# Sheet1.net
KiCad netlist of a schematic drawn in Altium Designer
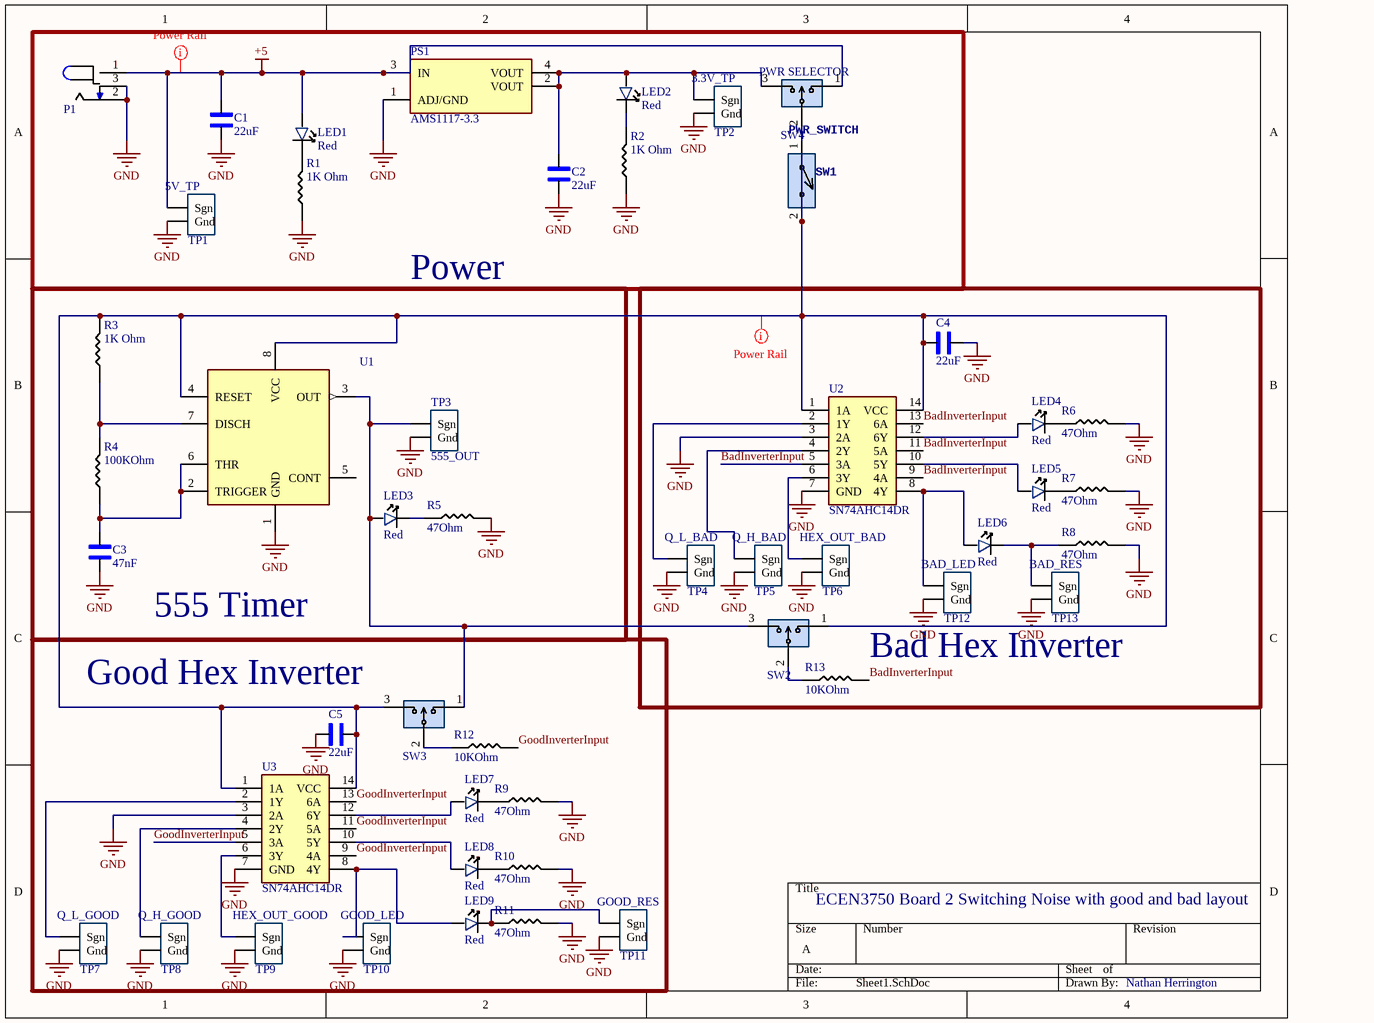
[diagram p0: Sheet1.SchDoc]

(export (version "E")
  (design (tool "Eeschema 10.0.6"))
  (components
    (comp (ref "C1")
      (value "22uF")
      (footprint "1206_Passive_Capacitor")
      (description "22uF ±10% 25V X5R 1206 Multilayer Ceramic Capacitors MLCC - SMD/SMT RoHS")
      (fields (field (name "MFR PART #") "CL31A226KAHNNNE") (field (name "LCSC PART#") "C12891"))
      (libsource (lib "ECEN5730Lib_2023_05_DS") (part "C_22uF_1206"))
    )
    (comp (ref "C2")
      (value "22uF")
      (footprint "1206_Passive_Capacitor")
      (description "22uF ±10% 25V X5R 1206 Multilayer Ceramic Capacitors MLCC - SMD/SMT RoHS")
      (fields (field (name "MFR PART #") "CL31A226KAHNNNE") (field (name "LCSC PART#") "C12891"))
      (libsource (lib "ECEN5730Lib_2023_05_DS") (part "C_22uF_1206"))
    )
    (comp (ref "C3")
      (value "47nF")
      (footprint "1206_Passive_Capacitor")
      (description "47nF ±5% 50V C0G 1206 Multilayer Ceramic Capacitors MLCC - SMD/SMT RoHS")
      (fields (field (name "LCSC PART#") "C21812") (field (name "MFR PART #") "GRM31M5C1H473JA01L"))
      (libsource (lib "ECEN5730Lib_2023_05_DS") (part "C_47nF_1206"))
    )
    (comp (ref "C4")
      (value "22uF")
      (footprint "1206_Passive_Capacitor")
      (description "22uF ±10% 25V X5R 1206 Multilayer Ceramic Capacitors MLCC - SMD/SMT RoHS")
      (fields (field (name "MFR PART #") "CL31A226KAHNNNE") (field (name "LCSC PART#") "C12891"))
      (libsource (lib "ECEN5730Lib_2023_05_DS") (part "C_22uF_1206"))
    )
    (comp (ref "C5")
      (value "22uF")
      (footprint "1206_Passive_Capacitor")
      (description "22uF ±10% 25V X5R 1206 Multilayer Ceramic Capacitors MLCC - SMD/SMT RoHS")
      (fields (field (name "MFR PART #") "CL31A226KAHNNNE") (field (name "LCSC PART#") "C12891"))
      (libsource (lib "ECEN5730Lib_2023_05_DS") (part "C_22uF_1206"))
    )
    (comp (ref "LED1")
      (value "Red")
      (footprint "LED_1206")
      (description "Red 621~631nm 1206 Light Emitting Diodes (LED) RoHS")
      (fields (field (name "MFR PART #") "15-21/R6C-FQ1R1B/2T") (field (name "LCSC PART#") "C93133"))
      (libsource (lib "ECEN5730Lib_2023_05_DS") (part "LED_RED_1206"))
    )
    (comp (ref "LED2")
      (value "Red")
      (footprint "LED_1206")
      (description "Red 621~631nm 1206 Light Emitting Diodes (LED) RoHS")
      (fields (field (name "MFR PART #") "15-21/R6C-FQ1R1B/2T") (field (name "LCSC PART#") "C93133"))
      (libsource (lib "ECEN5730Lib_2023_05_DS") (part "LED_RED_1206"))
    )
    (comp (ref "LED3")
      (value "Red")
      (footprint "LED_1206")
      (description "Red 621~631nm 1206 Light Emitting Diodes (LED) RoHS")
      (fields (field (name "MFR PART #") "15-21/R6C-FQ1R1B/2T") (field (name "LCSC PART#") "C93133"))
      (libsource (lib "ECEN5730Lib_2023_05_DS") (part "LED_RED_1206"))
    )
    (comp (ref "LED4")
      (value "Red")
      (footprint "LED_1206")
      (description "Red 621~631nm 1206 Light Emitting Diodes (LED) RoHS")
      (fields (field (name "MFR PART #") "15-21/R6C-FQ1R1B/2T") (field (name "LCSC PART#") "C93133"))
      (libsource (lib "ECEN5730Lib_2023_05_DS") (part "LED_RED_1206"))
    )
    (comp (ref "LED5")
      (value "Red")
      (footprint "LED_1206")
      (description "Red 621~631nm 1206 Light Emitting Diodes (LED) RoHS")
      (fields (field (name "MFR PART #") "15-21/R6C-FQ1R1B/2T") (field (name "LCSC PART#") "C93133"))
      (libsource (lib "ECEN5730Lib_2023_05_DS") (part "LED_RED_1206"))
    )
    (comp (ref "LED6")
      (value "Red")
      (footprint "LED_1206")
      (description "Red 621~631nm 1206 Light Emitting Diodes (LED) RoHS")
      (fields (field (name "MFR PART #") "15-21/R6C-FQ1R1B/2T") (field (name "LCSC PART#") "C93133"))
      (libsource (lib "ECEN5730Lib_2023_05_DS") (part "LED_RED_1206"))
    )
    (comp (ref "LED7")
      (value "Red")
      (footprint "LED_1206")
      (description "Red 621~631nm 1206 Light Emitting Diodes (LED) RoHS")
      (fields (field (name "MFR PART #") "15-21/R6C-FQ1R1B/2T") (field (name "LCSC PART#") "C93133"))
      (libsource (lib "ECEN5730Lib_2023_05_DS") (part "LED_RED_1206"))
    )
    (comp (ref "LED8")
      (value "Red")
      (footprint "LED_1206")
      (description "Red 621~631nm 1206 Light Emitting Diodes (LED) RoHS")
      (fields (field (name "MFR PART #") "15-21/R6C-FQ1R1B/2T") (field (name "LCSC PART#") "C93133"))
      (libsource (lib "ECEN5730Lib_2023_05_DS") (part "LED_RED_1206"))
    )
    (comp (ref "LED9")
      (value "Red")
      (footprint "LED_1206")
      (description "Red 621~631nm 1206 Light Emitting Diodes (LED) RoHS")
      (fields (field (name "MFR PART #") "15-21/R6C-FQ1R1B/2T") (field (name "LCSC PART#") "C93133"))
      (libsource (lib "ECEN5730Lib_2023_05_DS") (part "LED_RED_1206"))
    )
    (comp (ref "P1")
      (value "Power Jack")
      (footprint "Power_Jack")
      (description "Power Barrel Connector Jack 2.10mm ID (0.083\"), 5.50mm OD (0.217\") Through Hole, Right Angle")
      (fields (field (name "MFR PART #") "PJ-102A") (field (name "LCSC PART#") "C136744"))
      (libsource (lib "ECEN5730Lib_2023_05_DS") (part "P_Power Jack"))
    )
    (comp (ref "PS1")
      (value "AMS1117-3.3")
      (footprint "LDO")
      (description "LOW DROPOUT REGULATORS(LDO) POSITIVE FIXED 1.3V @ 800MA 15V 3.3V 1A SOT-223 ROHS")
      (fields (field (name "LCSC PART#") "C6186"))
      (libsource (lib "ECEN5730Lib_2023_05_DS") (part "PS_AMS_LDO_3v3"))
    )
    (comp (ref "R1")
      (value "1K Ohm")
      (footprint "1206_Passive_Resitor")
      (description "CHIP RESISTOR - SURFACE MOUNT 1KOHMS ±1% 1/4W 1206 ROHS")
      (fields (field (name "MFR PART #") "RNCP1206FTD1K00CT") (field (name "LCSC PART#") "C4410"))
      (libsource (lib "ECEN5730Lib_2023_05_DS") (part "R_1K_1206"))
    )
    (comp (ref "R2")
      (value "1K Ohm")
      (footprint "1206_Passive_Resitor")
      (description "CHIP RESISTOR - SURFACE MOUNT 1KOHMS ±1% 1/4W 1206 ROHS")
      (fields (field (name "MFR PART #") "RNCP1206FTD1K00CT") (field (name "LCSC PART#") "C4410"))
      (libsource (lib "ECEN5730Lib_2023_05_DS") (part "R_1K_1206"))
    )
    (comp (ref "R3")
      (value "1K Ohm")
      (footprint "1206_Passive_Resitor")
      (description "CHIP RESISTOR - SURFACE MOUNT 1KOHMS ±1% 1/4W 1206 ROHS")
      (fields (field (name "MFR PART #") "RNCP1206FTD1K00CT") (field (name "LCSC PART#") "C4410"))
      (libsource (lib "ECEN5730Lib_2023_05_DS") (part "R_1K_1206"))
    )
    (comp (ref "R4")
      (value "100KOhm")
      (footprint "1206_Passive_Resitor")
      (description "100kΩ ±1% 0.25W ±100ppm/℃ 1206 Chip Resistor - Surface Mount RoHS")
      (fields (field (name "LCSC PART#") "C17900") (field (name "MFR PART #") "1206W4F1003T5E"))
      (libsource (lib "ECEN5730Lib_2023_05_DS") (part "R_100KOhm_1206"))
    )
    (comp (ref "R5")
      (value "47Ohm")
      (footprint "1206_Passive_Resitor")
      (description "47Ω ±5% 0.25W ±200ppm/℃ 1206 Chip Resistor - Surface Mount RoHS")
      (fields (field (name "MFR PART #") "1206W4J0470T5E") (field (name "LCSC PART#") "C25384"))
      (libsource (lib "ECEN5730Lib_2023_05_DS") (part "R_47Ohm_1206"))
    )
    (comp (ref "R6")
      (value "47Ohm")
      (footprint "1206_Passive_Resitor")
      (description "47Ω ±5% 0.25W ±200ppm/℃ 1206 Chip Resistor - Surface Mount RoHS")
      (fields (field (name "MFR PART #") "1206W4J0470T5E") (field (name "LCSC PART#") "C25384"))
      (libsource (lib "ECEN5730Lib_2023_05_DS") (part "R_47Ohm_1206"))
    )
    (comp (ref "R7")
      (value "47Ohm")
      (footprint "1206_Passive_Resitor")
      (description "47Ω ±5% 0.25W ±200ppm/℃ 1206 Chip Resistor - Surface Mount RoHS")
      (fields (field (name "MFR PART #") "1206W4J0470T5E") (field (name "LCSC PART#") "C25384"))
      (libsource (lib "ECEN5730Lib_2023_05_DS") (part "R_47Ohm_1206"))
    )
    (comp (ref "R8")
      (value "47Ohm")
      (footprint "1206_Passive_Resitor")
      (description "47Ω ±5% 0.25W ±200ppm/℃ 1206 Chip Resistor - Surface Mount RoHS")
      (fields (field (name "MFR PART #") "1206W4J0470T5E") (field (name "LCSC PART#") "C25384"))
      (libsource (lib "ECEN5730Lib_2023_05_DS") (part "R_47Ohm_1206"))
    )
    (comp (ref "R9")
      (value "47Ohm")
      (footprint "1206_Passive_Resitor")
      (description "47Ω ±5% 0.25W ±200ppm/℃ 1206 Chip Resistor - Surface Mount RoHS")
      (fields (field (name "MFR PART #") "1206W4J0470T5E") (field (name "LCSC PART#") "C25384"))
      (libsource (lib "ECEN5730Lib_2023_05_DS") (part "R_47Ohm_1206"))
    )
    (comp (ref "R10")
      (value "47Ohm")
      (footprint "1206_Passive_Resitor")
      (description "47Ω ±5% 0.25W ±200ppm/℃ 1206 Chip Resistor - Surface Mount RoHS")
      (fields (field (name "MFR PART #") "1206W4J0470T5E") (field (name "LCSC PART#") "C25384"))
      (libsource (lib "ECEN5730Lib_2023_05_DS") (part "R_47Ohm_1206"))
    )
    (comp (ref "R11")
      (value "47Ohm")
      (footprint "1206_Passive_Resitor")
      (description "47Ω ±5% 0.25W ±200ppm/℃ 1206 Chip Resistor - Surface Mount RoHS")
      (fields (field (name "MFR PART #") "1206W4J0470T5E") (field (name "LCSC PART#") "C25384"))
      (libsource (lib "ECEN5730Lib_2023_05_DS") (part "R_47Ohm_1206"))
    )
    (comp (ref "R12")
      (value "10KOhm")
      (footprint "1206_Passive_Resitor")
      (description "10 kOhms ±5% 0.25W, 1/4W Chip Resistor 1206 (3216 Metric) Automotive AEC-Q200 Thick Film")
      (fields (field (name "MFR PART #") "RMCF1206FT10K0") (field (name "LCSC PART#") "C17902"))
      (libsource (lib "ECEN5730Lib_2023_05_DS") (part "R_10KOhm_1206"))
    )
    (comp (ref "R13")
      (value "10KOhm")
      (footprint "1206_Passive_Resitor")
      (description "10 kOhms ±5% 0.25W, 1/4W Chip Resistor 1206 (3216 Metric) Automotive AEC-Q200 Thick Film")
      (fields (field (name "MFR PART #") "RMCF1206FT10K0") (field (name "LCSC PART#") "C17902"))
      (libsource (lib "ECEN5730Lib_2023_05_DS") (part "R_10KOhm_1206"))
    )
    (comp (ref "SW1")
      (value "PWR_SWITCH")
      (footprint "2Pin-Header-Conn")
      (description "2Pin Header")
      (fields (field (name "LCSC PART#") "C124375"))
      (libsource (lib "ECEN5730Lib_2023_05_DS") (part "SW_2Pin_100mil_Switch"))
    )
    (comp (ref "SW2")
      (value "PREC003SAAN-RC")
      (footprint "3_PIN_100mil")
      (description "Connector Header Through Hole 3 position 0.100\" (2.54mm)")
      (fields (field (name "LCSC PART#") "C49257"))
      (libsource (lib "ECEN5730Lib_2023_05_DS") (part "SW_3Pin_100mil_Switch"))
    )
    (comp (ref "SW3")
      (value "PREC003SAAN-RC")
      (footprint "3_PIN_100mil")
      (description "Connector Header Through Hole 3 position 0.100\" (2.54mm)")
      (fields (field (name "LCSC PART#") "C49257"))
      (libsource (lib "ECEN5730Lib_2023_05_DS") (part "SW_3Pin_100mil_Switch"))
    )
    (comp (ref "SW4")
      (value "PWR SELECTOR")
      (footprint "3_PIN_100mil")
      (description "Connector Header Through Hole 3 position 0.100\" (2.54mm)")
      (fields (field (name "MFR PART #") "PREC003SAAN-RC") (field (name "LCSC PART#") "C49257"))
      (libsource (lib "ECEN5730Lib_2023_05_DS") (part "SW_3Pin_100mil_Switch"))
    )
    (comp (ref "TP1")
      (value "5V_TP")
      (footprint "TP10x_Probe")
      (description "Test Point 300 mil centers")
      (libsource (lib "ECEN5730Lib_2023_05_DS") (part "TP_10x_Probe"))
    )
    (comp (ref "TP2")
      (value "3.3V_TP")
      (footprint "TP10x_Probe")
      (description "Test Point 300 mil centers")
      (libsource (lib "ECEN5730Lib_2023_05_DS") (part "TP_10x_Probe"))
    )
    (comp (ref "TP3")
      (value "555_OUT")
      (footprint "TP10x_Probe")
      (description "Test Point 300 mil centers")
      (libsource (lib "ECEN5730Lib_2023_05_DS") (part "TP_10x_Probe"))
    )
    (comp (ref "TP4")
      (value "Q_L_BAD")
      (footprint "TP10x_Probe")
      (description "Test Point 300 mil centers")
      (libsource (lib "ECEN5730Lib_2023_05_DS") (part "TP_10x_Probe"))
    )
    (comp (ref "TP5")
      (value "Q_H_BAD")
      (footprint "TP10x_Probe")
      (description "Test Point 300 mil centers")
      (libsource (lib "ECEN5730Lib_2023_05_DS") (part "TP_10x_Probe"))
    )
    (comp (ref "TP6")
      (value "HEX_OUT_BAD")
      (footprint "TP10x_Probe")
      (description "Test Point 300 mil centers")
      (libsource (lib "ECEN5730Lib_2023_05_DS") (part "TP_10x_Probe"))
    )
    (comp (ref "TP7")
      (value "Q_L_GOOD")
      (footprint "TP10x_Probe")
      (description "Test Point 300 mil centers")
      (libsource (lib "ECEN5730Lib_2023_05_DS") (part "TP_10x_Probe"))
    )
    (comp (ref "TP8")
      (value "Q_H_GOOD")
      (footprint "TP10x_Probe")
      (description "Test Point 300 mil centers")
      (libsource (lib "ECEN5730Lib_2023_05_DS") (part "TP_10x_Probe"))
    )
    (comp (ref "TP9")
      (value "HEX_OUT_GOOD")
      (footprint "TP10x_Probe")
      (description "Test Point 300 mil centers")
      (libsource (lib "ECEN5730Lib_2023_05_DS") (part "TP_10x_Probe"))
    )
    (comp (ref "TP10")
      (value "GOOD_LED")
      (footprint "TP10x_Probe")
      (description "Test Point 300 mil centers")
      (libsource (lib "ECEN5730Lib_2023_05_DS") (part "TP_10x_Probe"))
    )
    (comp (ref "TP11")
      (value "GOOD_RES")
      (footprint "TP10x_Probe")
      (description "Test Point 300 mil centers")
      (libsource (lib "ECEN5730Lib_2023_05_DS") (part "TP_10x_Probe"))
    )
    (comp (ref "TP12")
      (value "BAD_LED")
      (footprint "TP10x_Probe")
      (description "Test Point 300 mil centers")
      (libsource (lib "ECEN5730Lib_2023_05_DS") (part "TP_10x_Probe"))
    )
    (comp (ref "TP13")
      (value "BAD_RES")
      (footprint "TP10x_Probe")
      (description "Test Point 300 mil centers")
      (libsource (lib "ECEN5730Lib_2023_05_DS") (part "TP_10x_Probe"))
    )
    (comp (ref "U1")
      (value "LMC555CMX/NOPB")
      (footprint "TS555IDTTR")
      (description "555 Type, Timer/Oscillator _Single_ IC 3MHz 8-SO")
      (fields (field (name "LCSC PART#") "C90760"))
      (libsource (lib "ECEN5730Lib_2023_05_DS") (part "U_555_Fast"))
    )
    (comp (ref "U2")
      (value "SN74AHC14DR")
      (footprint "HEX_74AC14")
      (description "Inverter IC 6 Channel Schmitt Trigger 14-SOIC")
      (fields (field (name "LCSC PART#") "C6942"))
      (libsource (lib "ECEN5730Lib_2023_05_DS") (part "U_74AHC14"))
    )
    (comp (ref "U3")
      (value "SN74AHC14DR")
      (footprint "HEX_74AC14")
      (description "Inverter IC 6 Channel Schmitt Trigger 14-SOIC")
      (fields (field (name "LCSC PART#") "C6942"))
      (libsource (lib "ECEN5730Lib_2023_05_DS") (part "U_74AHC14"))
    )
  )
  (nets
    (net (code "1") (name "+5") (class "Default")
      (node (ref "C1") (pin "2") (pinfunction "2_2") (pintype "passive"))
      (node (ref "LED1") (pin "1") (pinfunction "1_1") (pintype "passive"))
      (node (ref "P1") (pin "1") (pinfunction "1_1") (pintype "power_in"))
      (node (ref "PS1") (pin "3") (pinfunction "IN_3") (pintype "power_in"))
      (node (ref "SW4") (pin "1") (pinfunction "1_1") (pintype "passive"))
      (node (ref "TP1") (pin "1") (pinfunction "Sgn_1") (pintype "passive"))
    )
    (net (code "2") (name "/BadInverterInput") (class "Default")
      (node (ref "R13") (pin "2") (pinfunction "2_2") (pintype "passive"))
      (node (ref "U2") (pin "11") (pinfunction "5A_11") (pintype "passive"))
      (node (ref "U2") (pin "13") (pinfunction "6A_13") (pintype "passive"))
      (node (ref "U2") (pin "5") (pinfunction "3A_5") (pintype "passive"))
      (node (ref "U2") (pin "9") (pinfunction "4A_9") (pintype "passive"))
    )
    (net (code "3") (name "/GoodInverterInput") (class "Default")
      (node (ref "R12") (pin "2") (pinfunction "2_2") (pintype "passive"))
      (node (ref "U3") (pin "11") (pinfunction "5A_11") (pintype "passive"))
      (node (ref "U3") (pin "13") (pinfunction "6A_13") (pintype "passive"))
      (node (ref "U3") (pin "5") (pinfunction "3A_5") (pintype "passive"))
      (node (ref "U3") (pin "9") (pinfunction "4A_9") (pintype "passive"))
    )
    (net (code "4") (name "GND") (class "Default")
      (node (ref "C1") (pin "1") (pinfunction "1_1") (pintype "passive"))
      (node (ref "C2") (pin "1") (pinfunction "1_1") (pintype "passive"))
      (node (ref "C3") (pin "1") (pinfunction "1_1") (pintype "passive"))
      (node (ref "C4") (pin "2") (pinfunction "2_2") (pintype "passive"))
      (node (ref "C5") (pin "1") (pinfunction "1_1") (pintype "passive"))
      (node (ref "P1") (pin "2") (pinfunction "2_2") (pintype "power_in"))
      (node (ref "P1") (pin "3") (pinfunction "3_3") (pintype "power_in"))
      (node (ref "PS1") (pin "1") (pinfunction "ADJ/GND_1") (pintype "passive"))
      (node (ref "R1") (pin "1") (pinfunction "1_1") (pintype "passive"))
      (node (ref "R10") (pin "2") (pinfunction "2_2") (pintype "passive"))
      (node (ref "R11") (pin "2") (pinfunction "2_2") (pintype "passive"))
      (node (ref "R2") (pin "1") (pinfunction "1_1") (pintype "passive"))
      (node (ref "R5") (pin "2") (pinfunction "2_2") (pintype "passive"))
      (node (ref "R6") (pin "2") (pinfunction "2_2") (pintype "passive"))
      (node (ref "R7") (pin "2") (pinfunction "2_2") (pintype "passive"))
      (node (ref "R8") (pin "2") (pinfunction "2_2") (pintype "passive"))
      (node (ref "R9") (pin "2") (pinfunction "2_2") (pintype "passive"))
      (node (ref "TP1") (pin "2") (pinfunction "Gnd_2") (pintype "passive"))
      (node (ref "TP10") (pin "2") (pinfunction "Gnd_2") (pintype "passive"))
      (node (ref "TP11") (pin "2") (pinfunction "Gnd_2") (pintype "passive"))
      (node (ref "TP12") (pin "2") (pinfunction "Gnd_2") (pintype "passive"))
      (node (ref "TP13") (pin "2") (pinfunction "Gnd_2") (pintype "passive"))
      (node (ref "TP2") (pin "2") (pinfunction "Gnd_2") (pintype "passive"))
      (node (ref "TP3") (pin "2") (pinfunction "Gnd_2") (pintype "passive"))
      (node (ref "TP4") (pin "2") (pinfunction "Gnd_2") (pintype "passive"))
      (node (ref "TP5") (pin "2") (pinfunction "Gnd_2") (pintype "passive"))
      (node (ref "TP6") (pin "2") (pinfunction "Gnd_2") (pintype "passive"))
      (node (ref "TP7") (pin "2") (pinfunction "Gnd_2") (pintype "passive"))
      (node (ref "TP8") (pin "2") (pinfunction "Gnd_2") (pintype "passive"))
      (node (ref "TP9") (pin "2") (pinfunction "Gnd_2") (pintype "passive"))
      (node (ref "U1") (pin "1") (pinfunction "GND_1") (pintype "power_in"))
      (node (ref "U2") (pin "3") (pinfunction "2A_3") (pintype "passive"))
      (node (ref "U2") (pin "7") (pinfunction "GND_7") (pintype "passive"))
      (node (ref "U3") (pin "3") (pinfunction "2A_3") (pintype "passive"))
      (node (ref "U3") (pin "7") (pinfunction "GND_7") (pintype "passive"))
    )
    (net (code "5") (name "Net-(LED1-Pad2)") (class "Default")
      (node (ref "LED1") (pin "2") (pinfunction "2_2") (pintype "passive"))
      (node (ref "R1") (pin "2") (pinfunction "2_2") (pintype "passive"))
    )
    (net (code "6") (name "Net-(LED2-Pad2)") (class "Default")
      (node (ref "LED2") (pin "2") (pinfunction "2_2") (pintype "passive"))
      (node (ref "R2") (pin "2") (pinfunction "2_2") (pintype "passive"))
    )
    (net (code "7") (name "Net-(LED3-Pad2)") (class "Default")
      (node (ref "LED3") (pin "2") (pinfunction "2_2") (pintype "passive"))
      (node (ref "R5") (pin "1") (pinfunction "1_1") (pintype "passive"))
    )
    (net (code "8") (name "Net-(LED4-Pad2)") (class "Default")
      (node (ref "LED4") (pin "2") (pinfunction "2_2") (pintype "passive"))
      (node (ref "R6") (pin "1") (pinfunction "1_1") (pintype "passive"))
    )
    (net (code "9") (name "Net-(LED5-Pad2)") (class "Default")
      (node (ref "LED5") (pin "2") (pinfunction "2_2") (pintype "passive"))
      (node (ref "R7") (pin "1") (pinfunction "1_1") (pintype "passive"))
    )
    (net (code "10") (name "Net-(LED7-Pad2)") (class "Default")
      (node (ref "LED7") (pin "2") (pinfunction "2_2") (pintype "passive"))
      (node (ref "R9") (pin "1") (pinfunction "1_1") (pintype "passive"))
    )
    (net (code "11") (name "Net-(LED8-Pad2)") (class "Default")
      (node (ref "LED8") (pin "2") (pinfunction "2_2") (pintype "passive"))
      (node (ref "R10") (pin "1") (pinfunction "1_1") (pintype "passive"))
    )
    (net (code "12") (name "Net-(R12-Pad1)") (class "Default")
      (node (ref "R12") (pin "1") (pinfunction "1_1") (pintype "passive"))
      (node (ref "SW3") (pin "2") (pinfunction "2_2") (pintype "passive"))
    )
    (net (code "13") (name "Net-(R13-Pad1)") (class "Default")
      (node (ref "R13") (pin "1") (pinfunction "1_1") (pintype "passive"))
      (node (ref "SW2") (pin "2") (pinfunction "2_2") (pintype "passive"))
    )
    (net (code "14") (name "Net-(SW1-Pad1)") (class "Default")
      (node (ref "SW1") (pin "1") (pinfunction "1_1") (pintype "passive"))
      (node (ref "SW4") (pin "2") (pinfunction "2_2") (pintype "passive"))
    )
    (net (code "15") (name "Net-(TP2-Sgn)") (class "Default")
      (node (ref "C2") (pin "2") (pinfunction "2_2") (pintype "passive"))
      (node (ref "LED2") (pin "1") (pinfunction "1_1") (pintype "passive"))
      (node (ref "PS1") (pin "2") (pinfunction "VOUT_2") (pintype "power_in"))
      (node (ref "PS1") (pin "4") (pinfunction "VOUT_4") (pintype "power_in"))
      (node (ref "SW4") (pin "3") (pinfunction "3_3") (pintype "passive"))
      (node (ref "TP2") (pin "1") (pinfunction "Sgn_1") (pintype "passive"))
    )
    (net (code "16") (name "Net-(TP3-Sgn)") (class "Default")
      (node (ref "LED3") (pin "1") (pinfunction "1_1") (pintype "passive"))
      (node (ref "SW2") (pin "3") (pinfunction "3_3") (pintype "passive"))
      (node (ref "SW3") (pin "1") (pinfunction "1_1") (pintype "passive"))
      (node (ref "TP3") (pin "1") (pinfunction "Sgn_1") (pintype "passive"))
      (node (ref "U1") (pin "3") (pinfunction "OUT_3") (pintype "output"))
    )
    (net (code "17") (name "Net-(TP4-Sgn)") (class "Default")
      (node (ref "TP4") (pin "1") (pinfunction "Sgn_1") (pintype "passive"))
      (node (ref "U2") (pin "2") (pinfunction "1Y_2") (pintype "passive"))
    )
    (net (code "18") (name "Net-(TP5-Sgn)") (class "Default")
      (node (ref "TP5") (pin "1") (pinfunction "Sgn_1") (pintype "passive"))
      (node (ref "U2") (pin "4") (pinfunction "2Y_4") (pintype "passive"))
    )
    (net (code "19") (name "Net-(TP6-Sgn)") (class "Default")
      (node (ref "TP6") (pin "1") (pinfunction "Sgn_1") (pintype "passive"))
      (node (ref "U2") (pin "6") (pinfunction "3Y_6") (pintype "passive"))
    )
    (net (code "20") (name "Net-(TP7-Sgn)") (class "Default")
      (node (ref "TP7") (pin "1") (pinfunction "Sgn_1") (pintype "passive"))
      (node (ref "U3") (pin "2") (pinfunction "1Y_2") (pintype "passive"))
    )
    (net (code "21") (name "Net-(TP8-Sgn)") (class "Default")
      (node (ref "TP8") (pin "1") (pinfunction "Sgn_1") (pintype "passive"))
      (node (ref "U3") (pin "4") (pinfunction "2Y_4") (pintype "passive"))
    )
    (net (code "22") (name "Net-(TP9-Sgn)") (class "Default")
      (node (ref "TP9") (pin "1") (pinfunction "Sgn_1") (pintype "passive"))
      (node (ref "U3") (pin "6") (pinfunction "3Y_6") (pintype "passive"))
    )
    (net (code "23") (name "Net-(TP10-Sgn)") (class "Default")
      (node (ref "LED9") (pin "1") (pinfunction "1_1") (pintype "passive"))
      (node (ref "TP10") (pin "1") (pinfunction "Sgn_1") (pintype "passive"))
      (node (ref "U3") (pin "8") (pinfunction "4Y_8") (pintype "passive"))
    )
    (net (code "24") (name "Net-(TP11-Sgn)") (class "Default")
      (node (ref "LED9") (pin "2") (pinfunction "2_2") (pintype "passive"))
      (node (ref "R11") (pin "1") (pinfunction "1_1") (pintype "passive"))
      (node (ref "TP11") (pin "1") (pinfunction "Sgn_1") (pintype "passive"))
    )
    (net (code "25") (name "Net-(TP12-Sgn)") (class "Default")
      (node (ref "LED6") (pin "1") (pinfunction "1_1") (pintype "passive"))
      (node (ref "TP12") (pin "1") (pinfunction "Sgn_1") (pintype "passive"))
      (node (ref "U2") (pin "8") (pinfunction "4Y_8") (pintype "passive"))
    )
    (net (code "26") (name "Net-(TP13-Sgn)") (class "Default")
      (node (ref "LED6") (pin "2") (pinfunction "2_2") (pintype "passive"))
      (node (ref "R8") (pin "1") (pinfunction "1_1") (pintype "passive"))
      (node (ref "TP13") (pin "1") (pinfunction "Sgn_1") (pintype "passive"))
    )
    (net (code "27") (name "Net-(U1-DISCH)") (class "Default")
      (node (ref "R3") (pin "1") (pinfunction "1_1") (pintype "passive"))
      (node (ref "R4") (pin "2") (pinfunction "2_2") (pintype "passive"))
      (node (ref "U1") (pin "7") (pinfunction "DISCH_7") (pintype "passive"))
    )
    (net (code "28") (name "Net-(U1-RESET)") (class "Default")
      (node (ref "C4") (pin "1") (pinfunction "1_1") (pintype "passive"))
      (node (ref "C5") (pin "2") (pinfunction "2_2") (pintype "passive"))
      (node (ref "R3") (pin "2") (pinfunction "2_2") (pintype "passive"))
      (node (ref "SW1") (pin "2") (pinfunction "2_2") (pintype "passive"))
      (node (ref "SW2") (pin "1") (pinfunction "1_1") (pintype "passive"))
      (node (ref "SW3") (pin "3") (pinfunction "3_3") (pintype "passive"))
      (node (ref "U1") (pin "4") (pinfunction "RESET_4") (pintype "passive"))
      (node (ref "U1") (pin "8") (pinfunction "VCC_8") (pintype "power_in"))
      (node (ref "U2") (pin "1") (pinfunction "1A_1") (pintype "passive"))
      (node (ref "U2") (pin "14") (pinfunction "VCC_14") (pintype "passive"))
      (node (ref "U3") (pin "1") (pinfunction "1A_1") (pintype "passive"))
      (node (ref "U3") (pin "14") (pinfunction "VCC_14") (pintype "passive"))
    )
    (net (code "29") (name "Net-(U1-THR)") (class "Default")
      (node (ref "C3") (pin "2") (pinfunction "2_2") (pintype "passive"))
      (node (ref "R4") (pin "1") (pinfunction "1_1") (pintype "passive"))
      (node (ref "U1") (pin "2") (pinfunction "TRIGGER_2") (pintype "passive"))
      (node (ref "U1") (pin "6") (pinfunction "THR_6") (pintype "passive"))
    )
    (net (code "30") (name "Net-(U2-5Y)") (class "Default")
      (node (ref "LED5") (pin "1") (pinfunction "1_1") (pintype "passive"))
      (node (ref "U2") (pin "10") (pinfunction "5Y_10") (pintype "passive"))
    )
    (net (code "31") (name "Net-(U2-6Y)") (class "Default")
      (node (ref "LED4") (pin "1") (pinfunction "1_1") (pintype "passive"))
      (node (ref "U2") (pin "12") (pinfunction "6Y_12") (pintype "passive"))
    )
    (net (code "32") (name "Net-(U3-5Y)") (class "Default")
      (node (ref "LED8") (pin "1") (pinfunction "1_1") (pintype "passive"))
      (node (ref "U3") (pin "10") (pinfunction "5Y_10") (pintype "passive"))
    )
    (net (code "33") (name "Net-(U3-6Y)") (class "Default")
      (node (ref "LED7") (pin "1") (pinfunction "1_1") (pintype "passive"))
      (node (ref "U3") (pin "12") (pinfunction "6Y_12") (pintype "passive"))
    )
    (net (code "34") (name "unconnected-(U1-CONT-Pad5)") (class "Default")
      (node (ref "U1") (pin "5") (pinfunction "CONT_5") (pintype "passive"))
    )
  )
)
